# FPGA_Video_Windows.net
KiCad netlist of a schematic drawn in Altium Designer
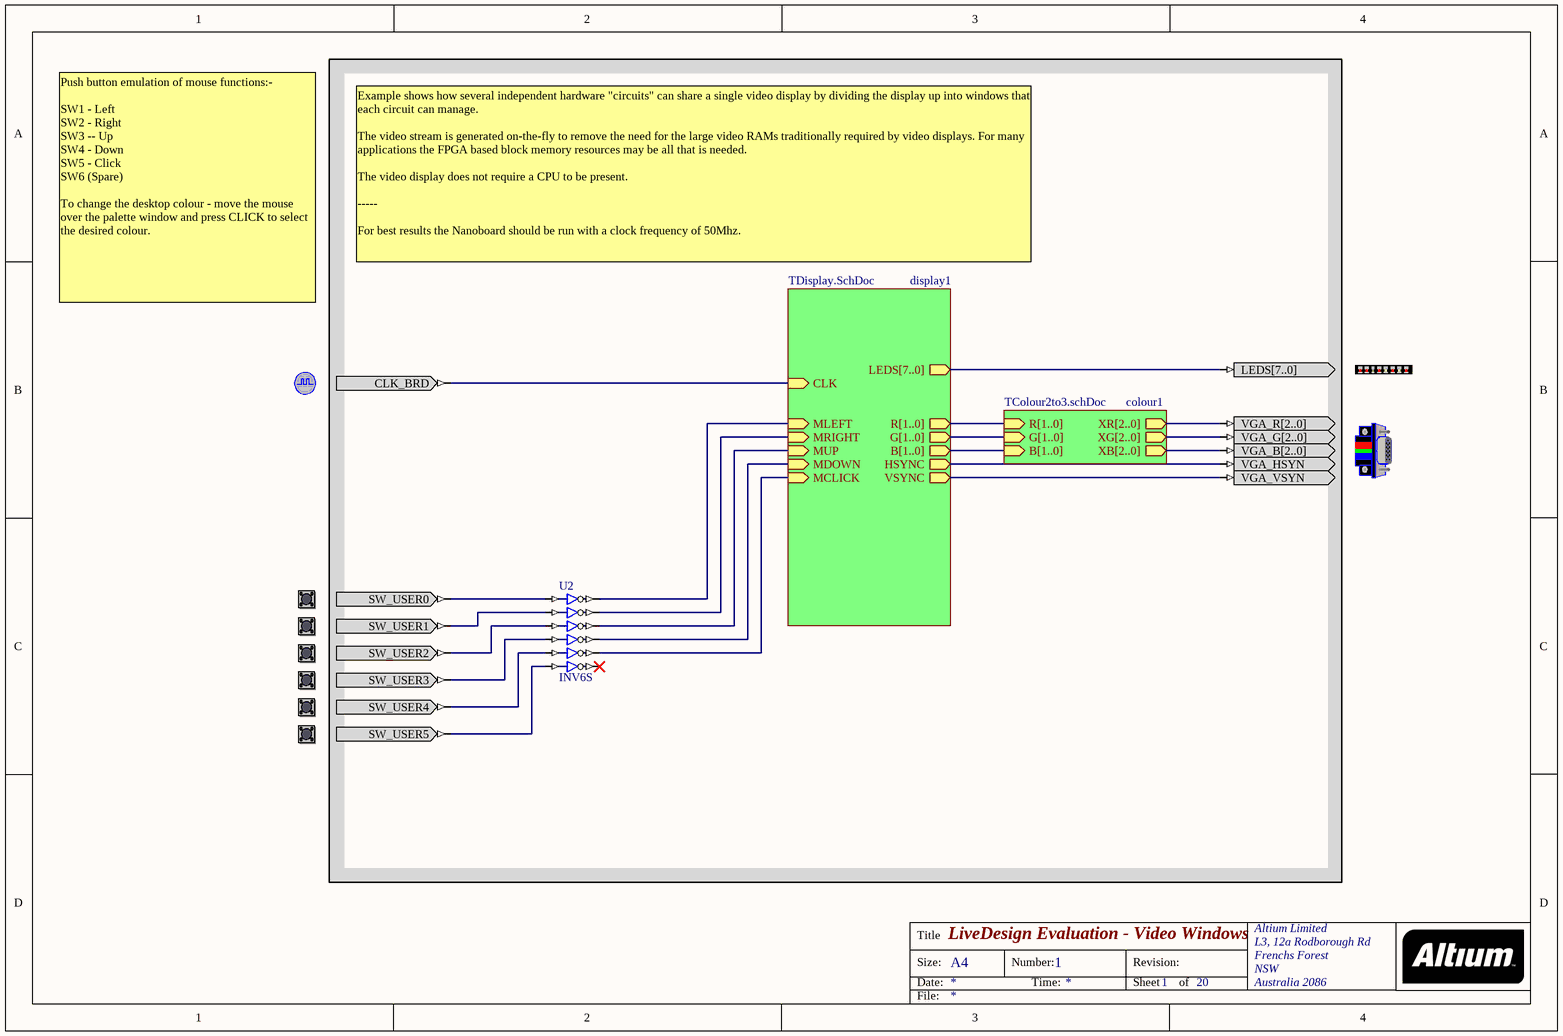
[diagram p0: FPGA_Video_Windows.SchDoc]

(export (version "E")
  (design (tool "Eeschema 10.0.6"))
  (components
    (comp (ref "CLOCK_BOARD")
      (value "CLOCK_BOARD")
      (description "Global System Clock Supply")
      (fields (field (name "PUBLISHER") "Altium Limited"))
      (libsource (lib "FPGA EvalBoard Port-Plugin") (part "CLOCK_BOARD"))
    )
    (comp (ref "LED")
      (value "LED")
      (description "8-Way LEDS")
      (fields (field (name "PUBLISHER") "Altium Limited"))
      (libsource (lib "FPGA EvalBoard Port-Plugin") (part "LED"))
    )
    (comp (ref "U2")
      (value "INV6S")
      (description "6-Bit Inverter, Single Pin Version")
      (fields (field (name "PUBLISHER") "Altium Limited"))
      (libsource (lib "FPGA Generic") (part "INV6S"))
    )
    (comp (ref "USER_BUTTONX6")
      (value "USER_BUTTONX6")
      (description "User Buttons")
      (fields (field (name "PUBLISHER") "Altium Limited"))
      (libsource (lib "FPGA EvalBoard Port-Plugin") (part "USER_BUTTONX6"))
    )
    (comp (ref "VGACNTR")
      (value "VGACNTR")
      (description "VGA Dsub-15-Female-HD")
      (fields (field (name "PUBLISHER") "Altium Limited"))
      (libsource (lib "FPGA EvalBoard Port-Plugin") (part "VGACNTR"))
    )
  )
  (nets
    (net (code "2") (name "/CLK") (class "Default")
      (node (ref "CLOCK_BOARD") (pin "CLK_BRD") (pinfunction "CLK_BRD_CLK_BRD") (pintype "output"))
    )
    (net (code "4") (name "/HSYNC") (class "Default")
      (node (ref "VGACNTR") (pin "VGA_HSYN") (pinfunction "VGA_HSYN_VGA_HSYN") (pintype "input"))
    )
    (net (code "5") (name "/LEDS[7..0]") (class "Default")
      (node (ref "LED") (pin "LEDS[7..0]") (pinfunction "LEDS[7..0]_LEDS[7..0]") (pintype "input"))
    )
    (net (code "6") (name "/MCLICK") (class "Default")
      (node (ref "U2") (pin "O4") (pinfunction "O4_O4") (pintype "output"))
    )
    (net (code "7") (name "/MDOWN") (class "Default")
      (node (ref "U2") (pin "O3") (pinfunction "O3_O3") (pintype "output"))
    )
    (net (code "8") (name "/MLEFT") (class "Default")
      (node (ref "U2") (pin "O0") (pinfunction "O0_O0") (pintype "output"))
    )
    (net (code "9") (name "/MRIGHT") (class "Default")
      (node (ref "U2") (pin "O1") (pinfunction "O1_O1") (pintype "output"))
    )
    (net (code "10") (name "/MUP") (class "Default")
      (node (ref "U2") (pin "O2") (pinfunction "O2_O2") (pintype "output"))
    )
    (net (code "12") (name "/VSYNC") (class "Default")
      (node (ref "VGACNTR") (pin "VGA_VSYN") (pinfunction "VGA_VSYN_VGA_VSYN") (pintype "input"))
    )
    (net (code "13") (name "/XB[2..0]") (class "Default")
      (node (ref "VGACNTR") (pin "VGA_B[2..0]") (pinfunction "VGA_B[2..0]_VGA_B[2..0]") (pintype "input"))
    )
    (net (code "14") (name "/XG[2..0]") (class "Default")
      (node (ref "VGACNTR") (pin "VGA_G[2..0]") (pinfunction "VGA_G[2..0]_VGA_G[2..0]") (pintype "input"))
    )
    (net (code "15") (name "/XR[2..0]") (class "Default")
      (node (ref "VGACNTR") (pin "VGA_R[2..0]") (pinfunction "VGA_R[2..0]_VGA_R[2..0]") (pintype "input"))
    )
    (net (code "16") (name "Net-(U2-PadI0)") (class "Default")
      (node (ref "U2") (pin "I0") (pinfunction "I0_I0") (pintype "input"))
      (node (ref "USER_BUTTONX6") (pin "SW_USER0") (pinfunction "SW_USER0_SW_USER0") (pintype "output"))
    )
    (net (code "17") (name "Net-(U2-PadI1)") (class "Default")
      (node (ref "U2") (pin "I1") (pinfunction "I1_I1") (pintype "input"))
      (node (ref "USER_BUTTONX6") (pin "SW_USER1") (pinfunction "SW_USER1_SW_USER1") (pintype "output"))
    )
    (net (code "18") (name "Net-(U2-PadI2)") (class "Default")
      (node (ref "U2") (pin "I2") (pinfunction "I2_I2") (pintype "input"))
      (node (ref "USER_BUTTONX6") (pin "SW_USER2") (pinfunction "SW_USER2_SW_USER2") (pintype "output"))
    )
    (net (code "19") (name "Net-(U2-PadI3)") (class "Default")
      (node (ref "U2") (pin "I3") (pinfunction "I3_I3") (pintype "input"))
      (node (ref "USER_BUTTONX6") (pin "SW_USER3") (pinfunction "SW_USER3_SW_USER3") (pintype "output"))
    )
    (net (code "20") (name "Net-(U2-PadI4)") (class "Default")
      (node (ref "U2") (pin "I4") (pinfunction "I4_I4") (pintype "input"))
      (node (ref "USER_BUTTONX6") (pin "SW_USER4") (pinfunction "SW_USER4_SW_USER4") (pintype "output"))
    )
    (net (code "21") (name "Net-(U2-PadI5)") (class "Default")
      (node (ref "U2") (pin "I5") (pinfunction "I5_I5") (pintype "input"))
      (node (ref "USER_BUTTONX6") (pin "SW_USER5") (pinfunction "SW_USER5_SW_USER5") (pintype "output"))
    )
    (net (code "22") (name "unconnected-(U2-PadO5)") (class "Default")
      (node (ref "U2") (pin "O5") (pinfunction "O5_O5") (pintype "output+no_connect"))
    )
  )
)
